# nrf.net
KiCad netlist of a schematic drawn in Altium Designer
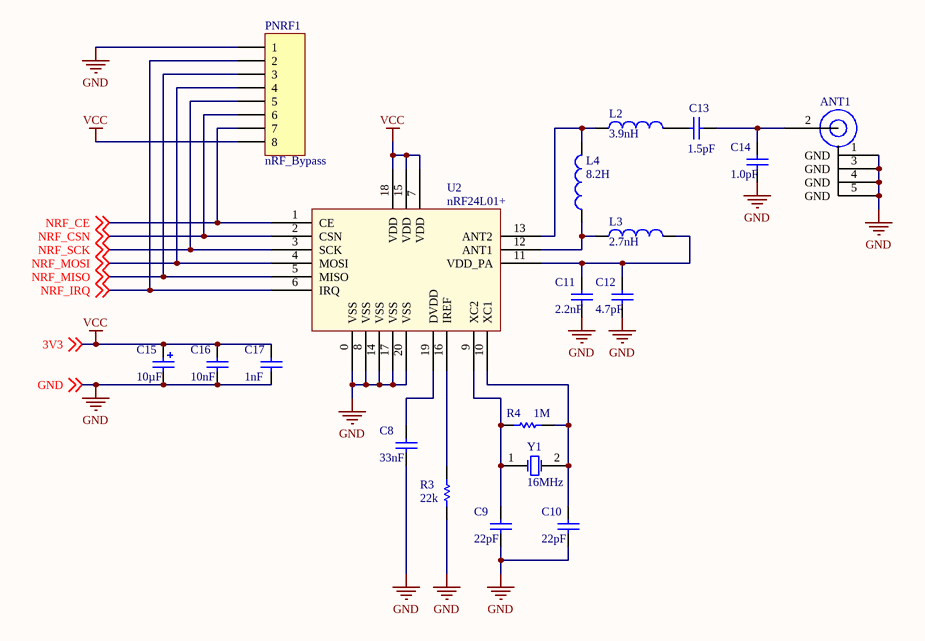
[diagram p0: nrf.SchDoc]

(export (version "E")
  (design (tool "Eeschema 10.0.6"))
  (components
    (comp (ref "ANT1")
      (value "Connector")
      (footprint "RP-SMA")
      (libsource (lib "antenna") (part "Antenna_Connector"))
    )
    (comp (ref "C8")
      (value "33nF")
      (footprint "0805-C")
      (description "Capacitor")
      (fields (field (name "Comment") "Cap") (field (name "PUBLISHER") "Altium Limited"))
      (libsource (lib "Miscellaneous Devices") (part "Cap"))
    )
    (comp (ref "C9")
      (value "22pF")
      (footprint "0805-C")
      (description "Capacitor")
      (fields (field (name "Comment") "Cap") (field (name "PUBLISHER") "Altium Limited"))
      (libsource (lib "Miscellaneous Devices") (part "Cap"))
    )
    (comp (ref "C10")
      (value "22pF")
      (footprint "0805-C")
      (description "Capacitor")
      (fields (field (name "Comment") "Cap") (field (name "PUBLISHER") "Altium Limited"))
      (libsource (lib "Miscellaneous Devices") (part "Cap"))
    )
    (comp (ref "C11")
      (value "2.2nF")
      (footprint "0805-C")
      (description "Capacitor")
      (fields (field (name "Comment") "Cap") (field (name "PUBLISHER") "Altium Limited"))
      (libsource (lib "Miscellaneous Devices") (part "Cap"))
    )
    (comp (ref "C12")
      (value "4.7pF")
      (footprint "0805-C")
      (description "Capacitor")
      (fields (field (name "Comment") "Cap") (field (name "PUBLISHER") "Altium Limited"))
      (libsource (lib "Miscellaneous Devices") (part "Cap"))
    )
    (comp (ref "C13")
      (value "1.5pF")
      (footprint "0805-C")
      (description "Capacitor")
      (fields (field (name "Comment") "Cap") (field (name "PUBLISHER") "Altium Limited"))
      (libsource (lib "Miscellaneous Devices") (part "Cap"))
    )
    (comp (ref "C14")
      (value "1.0pF")
      (footprint "0805-C")
      (description "Capacitor")
      (fields (field (name "Comment") "Cap") (field (name "PUBLISHER") "Altium Limited"))
      (libsource (lib "Miscellaneous Devices") (part "Cap"))
    )
    (comp (ref "C15")
      (value "10µF")
      (footprint "0805-TC")
      (description "Polarized Capacitor (Radial)")
      (fields (field (name "Comment") "Cap Pol1") (field (name "PUBLISHER") "Altium Limited"))
      (libsource (lib "Miscellaneous Devices") (part "Cap Pol1"))
    )
    (comp (ref "C16")
      (value "10nF")
      (footprint "0805-C")
      (description "Capacitor")
      (fields (field (name "Comment") "Cap") (field (name "PUBLISHER") "Altium Limited"))
      (libsource (lib "Miscellaneous Devices") (part "Cap"))
    )
    (comp (ref "C17")
      (value "1nF")
      (footprint "0805-C")
      (description "Capacitor")
      (fields (field (name "Comment") "Cap") (field (name "PUBLISHER") "Altium Limited"))
      (libsource (lib "Miscellaneous Devices") (part "Cap"))
    )
    (comp (ref "L2")
      (value "3.9nH")
      (footprint "0402-L")
      (description "Inductor")
      (fields (field (name "PUBLISHER") "Altium Limited"))
      (libsource (lib "Miscellaneous Devices") (part "Inductor"))
    )
    (comp (ref "L3")
      (value "2.7nH")
      (footprint "0402-L")
      (description "Inductor")
      (fields (field (name "PUBLISHER") "Altium Limited"))
      (libsource (lib "Miscellaneous Devices") (part "Inductor"))
    )
    (comp (ref "L4")
      (value "8.2H")
      (footprint "0402-L")
      (description "Inductor")
      (fields (field (name "PUBLISHER") "Altium Limited"))
      (libsource (lib "Miscellaneous Devices") (part "Inductor"))
    )
    (comp (ref "PNRF1")
      (value "nRF_Bypass")
      (footprint "HDR1X8")
      (description "Header, 8-Pin")
      (fields (field (name "PUBLISHER") "Altium Limited"))
      (libsource (lib "Miscellaneous Connectors") (part "Header 8"))
    )
    (comp (ref "R3")
      (value "22k")
      (footprint "0805-R")
      (description "Resistor")
      (fields (field (name "Comment") "Res1") (field (name "PUBLISHER") "Altium Limited"))
      (libsource (lib "Miscellaneous Devices") (part "Res1"))
    )
    (comp (ref "R4")
      (value "1M")
      (footprint "0805-R")
      (description "Resistor")
      (fields (field (name "Comment") "Res1") (field (name "PUBLISHER") "Altium Limited"))
      (libsource (lib "Miscellaneous Devices") (part "Res1"))
    )
    (comp (ref "U2")
      (value "nRF24L01+")
      (footprint "QFN50P400X400X95_HS-21N")
      (libsource (lib "nRF24L01+") (part "nRF24L01+"))
    )
    (comp (ref "Y1")
      (value "16MHz")
      (footprint "DFNCRY")
      (description "Crystal Oscillator")
      (fields (field (name "PUBLISHER") "Altium Limited"))
      (libsource (lib "Miscellaneous Devices") (part "XTAL"))
    )
  )
  (nets
    (net (code "1") (name "3V3") (class "Default")
      (node (ref "C15") (pin "1") (pinfunction "1_1") (pintype "passive"))
      (node (ref "C16") (pin "2") (pinfunction "2_2") (pintype "passive"))
      (node (ref "C17") (pin "2") (pinfunction "2_2") (pintype "passive"))
      (node (ref "PNRF1") (pin "8") (pinfunction "8_8") (pintype "passive"))
      (node (ref "U2") (pin "15") (pinfunction "VDD_15") (pintype "passive"))
      (node (ref "U2") (pin "18") (pinfunction "VDD_18") (pintype "passive"))
      (node (ref "U2") (pin "7") (pinfunction "VDD_7") (pintype "passive"))
    )
    (net (code "2") (name "GND") (class "Default")
      (node (ref "ANT1") (pin "1") (pinfunction "GND_1") (pintype "passive"))
      (node (ref "ANT1") (pin "3") (pinfunction "GND_3") (pintype "passive"))
      (node (ref "ANT1") (pin "4") (pinfunction "GND_4") (pintype "passive"))
      (node (ref "ANT1") (pin "5") (pinfunction "GND_5") (pintype "passive"))
      (node (ref "C10") (pin "1") (pinfunction "1_1") (pintype "passive"))
      (node (ref "C11") (pin "1") (pinfunction "1_1") (pintype "passive"))
      (node (ref "C12") (pin "1") (pinfunction "1_1") (pintype "passive"))
      (node (ref "C14") (pin "1") (pinfunction "1_1") (pintype "passive"))
      (node (ref "C15") (pin "2") (pinfunction "2_2") (pintype "passive"))
      (node (ref "C16") (pin "1") (pinfunction "1_1") (pintype "passive"))
      (node (ref "C17") (pin "1") (pinfunction "1_1") (pintype "passive"))
      (node (ref "C8") (pin "1") (pinfunction "1_1") (pintype "passive"))
      (node (ref "C9") (pin "1") (pinfunction "1_1") (pintype "passive"))
      (node (ref "PNRF1") (pin "1") (pinfunction "1_1") (pintype "passive"))
      (node (ref "R3") (pin "1") (pinfunction "1_1") (pintype "passive"))
      (node (ref "U2") (pin "0") (pinfunction "VSS_0") (pintype "passive"))
      (node (ref "U2") (pin "14") (pinfunction "VSS_14") (pintype "passive"))
      (node (ref "U2") (pin "17") (pinfunction "VSS_17") (pintype "passive"))
      (node (ref "U2") (pin "20") (pinfunction "VSS_20") (pintype "passive"))
      (node (ref "U2") (pin "8") (pinfunction "VSS_8") (pintype "passive"))
    )
    (net (code "3") (name "NRF_CE") (class "Default")
      (node (ref "PNRF1") (pin "7") (pinfunction "7_7") (pintype "passive"))
      (node (ref "U2") (pin "1") (pinfunction "CE_1") (pintype "passive"))
    )
    (net (code "4") (name "NRF_CSN") (class "Default")
      (node (ref "PNRF1") (pin "6") (pinfunction "6_6") (pintype "passive"))
      (node (ref "U2") (pin "2") (pinfunction "CSN_2") (pintype "passive"))
    )
    (net (code "5") (name "NRF_IRQ") (class "Default")
      (node (ref "PNRF1") (pin "2") (pinfunction "2_2") (pintype "passive"))
      (node (ref "U2") (pin "6") (pinfunction "IRQ_6") (pintype "passive"))
    )
    (net (code "6") (name "NRF_MISO") (class "Default")
      (node (ref "PNRF1") (pin "3") (pinfunction "3_3") (pintype "passive"))
      (node (ref "U2") (pin "5") (pinfunction "MISO_5") (pintype "passive"))
    )
    (net (code "7") (name "NRF_MOSI") (class "Default")
      (node (ref "PNRF1") (pin "4") (pinfunction "4_4") (pintype "passive"))
      (node (ref "U2") (pin "4") (pinfunction "MOSI_4") (pintype "passive"))
    )
    (net (code "8") (name "NRF_SCK") (class "Default")
      (node (ref "PNRF1") (pin "5") (pinfunction "5_5") (pintype "passive"))
      (node (ref "U2") (pin "3") (pinfunction "SCK_3") (pintype "passive"))
    )
    (net (code "9") (name "Net-(ANT1-ANT)") (class "Default")
      (node (ref "ANT1") (pin "2") (pinfunction "ANT_2") (pintype "passive"))
      (node (ref "C13") (pin "2") (pinfunction "2_2") (pintype "passive"))
      (node (ref "C14") (pin "2") (pinfunction "2_2") (pintype "passive"))
    )
    (net (code "10") (name "Net-(C13-Pad1)") (class "Default")
      (node (ref "C13") (pin "1") (pinfunction "1_1") (pintype "passive"))
      (node (ref "L2") (pin "2") (pinfunction "2_2") (pintype "passive"))
    )
    (net (code "11") (name "Net-(U2-ANT1)") (class "Default")
      (node (ref "L3") (pin "1") (pinfunction "1_1") (pintype "passive"))
      (node (ref "L4") (pin "1") (pinfunction "1_1") (pintype "passive"))
      (node (ref "U2") (pin "12") (pinfunction "ANT1_12") (pintype "passive"))
    )
    (net (code "12") (name "Net-(U2-ANT2)") (class "Default")
      (node (ref "L2") (pin "1") (pinfunction "1_1") (pintype "passive"))
      (node (ref "L4") (pin "2") (pinfunction "2_2") (pintype "passive"))
      (node (ref "U2") (pin "13") (pinfunction "ANT2_13") (pintype "passive"))
    )
    (net (code "13") (name "Net-(U2-DVDD)") (class "Default")
      (node (ref "C8") (pin "2") (pinfunction "2_2") (pintype "passive"))
      (node (ref "U2") (pin "19") (pinfunction "DVDD_19") (pintype "passive"))
    )
    (net (code "14") (name "Net-(U2-IREF)") (class "Default")
      (node (ref "R3") (pin "2") (pinfunction "2_2") (pintype "passive"))
      (node (ref "U2") (pin "16") (pinfunction "IREF_16") (pintype "passive"))
    )
    (net (code "15") (name "Net-(U2-VDD_PA)") (class "Default")
      (node (ref "C11") (pin "2") (pinfunction "2_2") (pintype "passive"))
      (node (ref "C12") (pin "2") (pinfunction "2_2") (pintype "passive"))
      (node (ref "L3") (pin "2") (pinfunction "2_2") (pintype "passive"))
      (node (ref "U2") (pin "11") (pinfunction "VDD_PA_11") (pintype "passive"))
    )
    (net (code "16") (name "Net-(U2-XC1)") (class "Default")
      (node (ref "C10") (pin "2") (pinfunction "2_2") (pintype "passive"))
      (node (ref "R4") (pin "2") (pinfunction "2_2") (pintype "passive"))
      (node (ref "U2") (pin "10") (pinfunction "XC1_10") (pintype "passive"))
      (node (ref "Y1") (pin "2") (pinfunction "OSC2_2") (pintype "passive"))
    )
    (net (code "17") (name "Net-(U2-XC2)") (class "Default")
      (node (ref "C9") (pin "2") (pinfunction "2_2") (pintype "passive"))
      (node (ref "R4") (pin "1") (pinfunction "1_1") (pintype "passive"))
      (node (ref "U2") (pin "9") (pinfunction "XC2_9") (pintype "passive"))
      (node (ref "Y1") (pin "1") (pinfunction "OSC1_1") (pintype "passive"))
    )
  )
)
